# Diagrama_prima_rio_NOVO.net
KiCad netlist of a schematic drawn in EAGLE
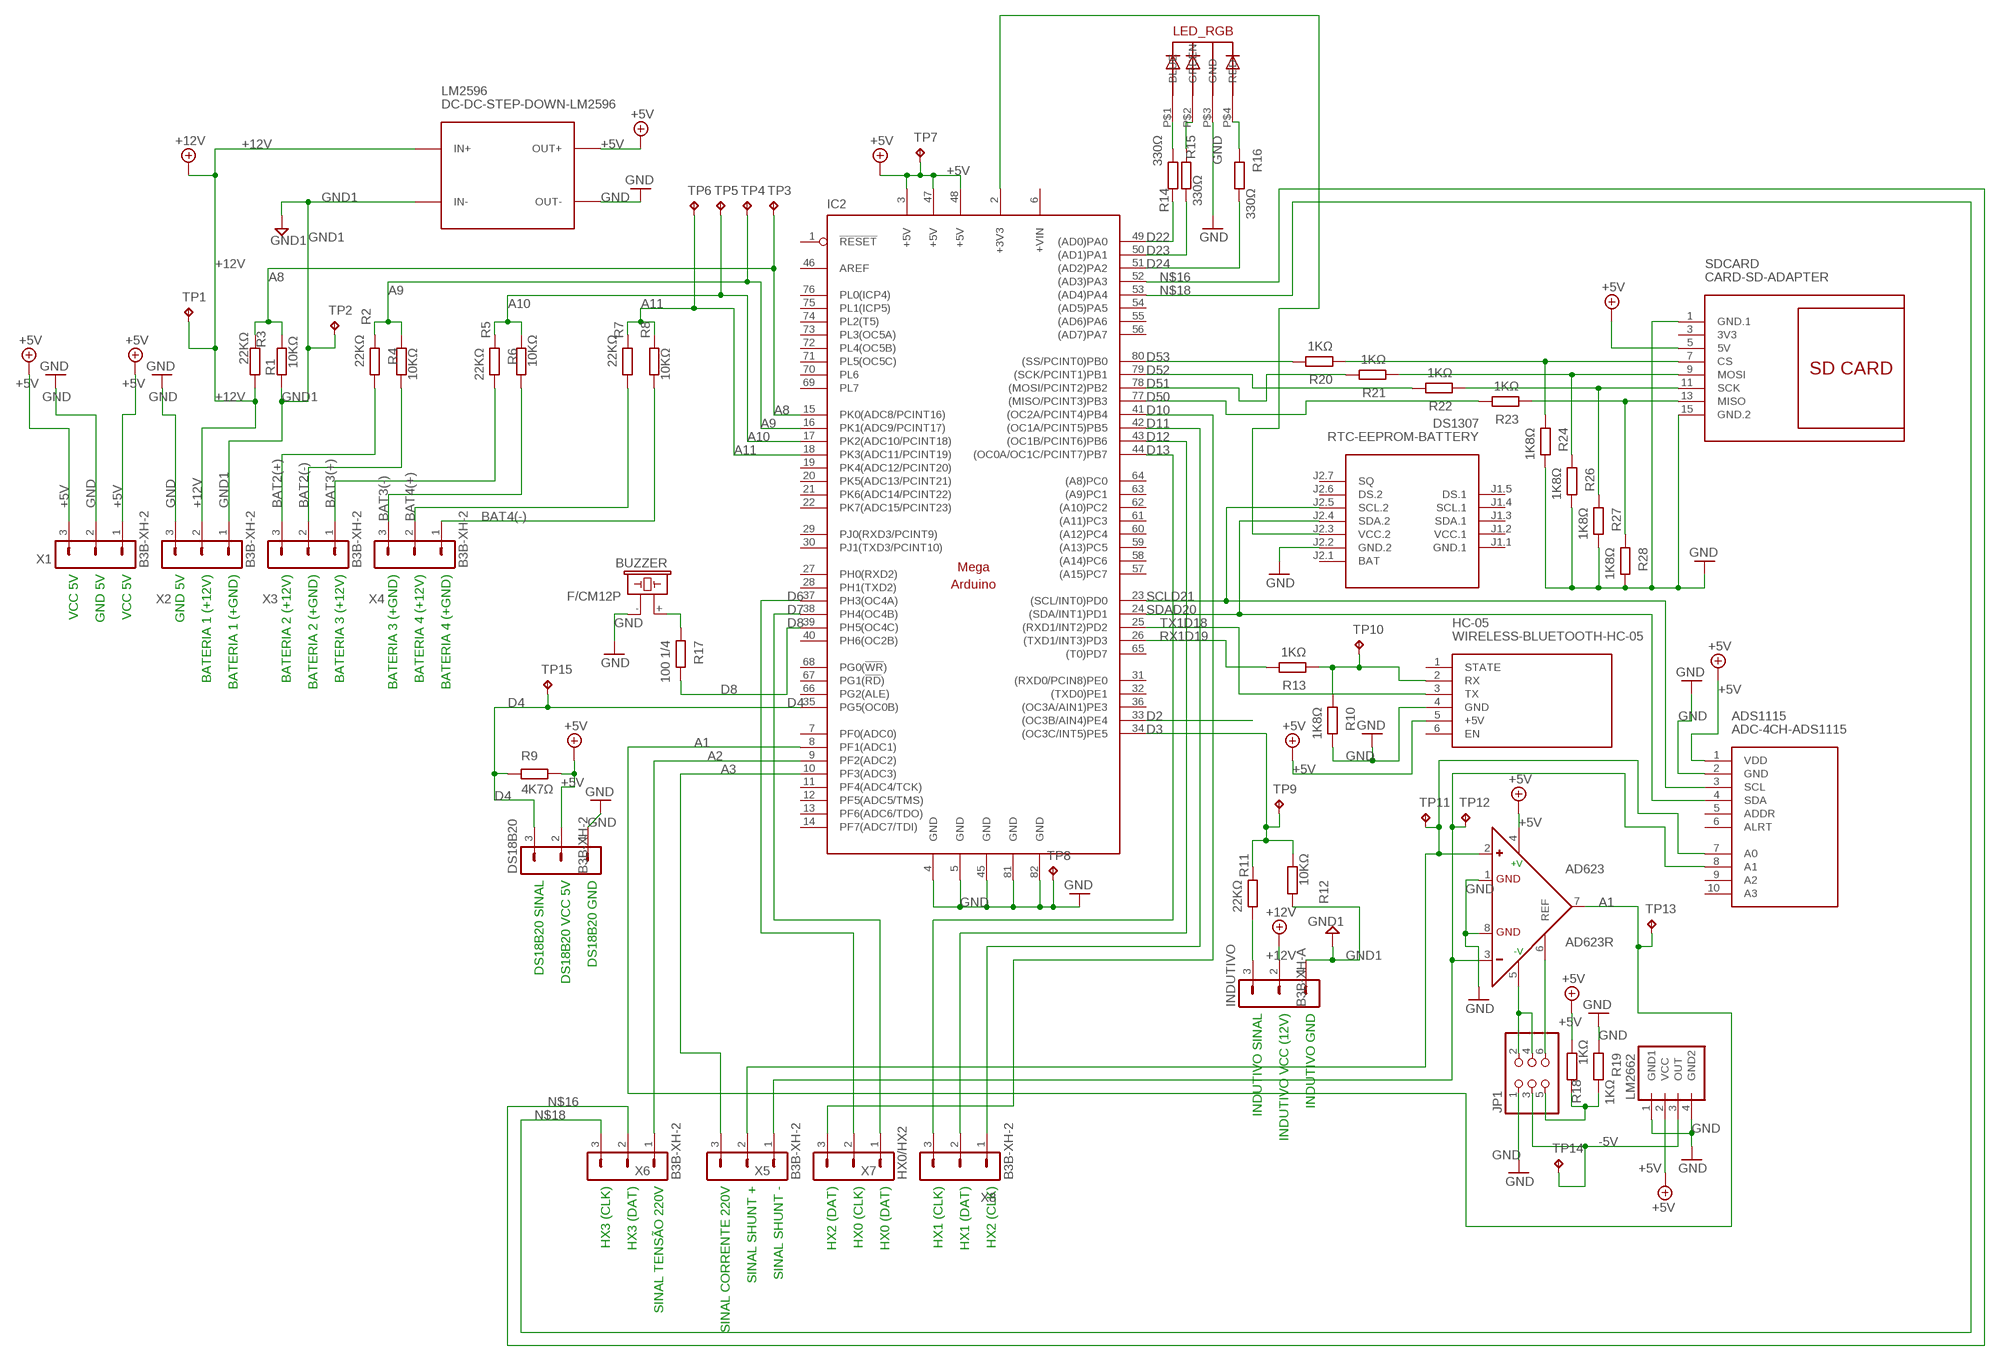
[diagram p0: schematic, sheet 1]

(export (version "E")
  (design (tool "Eeschema 10.0.6"))
  (components
    (comp (ref "AD623")
      (value "AD623R")
      (footprint "eagle-import:SO8")
      (fields (field (name "MPN") "AD623ARZ."))
      (libsource (lib "eagle-import") (part "AD623R"))
    )
    (comp (ref "ADS1115")
      (value "ADC-4CH-ADS1115")
      (footprint "eagle-import:ADC-4CH-ADS1115")
      (libsource (lib "eagle-import") (part "ADC-4CH-ADS1115"))
    )
    (comp (ref "BUZZER")
      (value "F/CM12P")
      (footprint "eagle-import:F_CM12P")
      (libsource (lib "eagle-import") (part "F/CM12P"))
    )
    (comp (ref "DS18B20")
      (value "B3B-XH-2")
      (footprint "eagle-import:B3B-XH-A")
      (libsource (lib "eagle-import") (part "B3B-XH-2"))
    )
    (comp (ref "DS1307")
      (value "RTC-EEPROM-BATTERY")
      (footprint "eagle-import:RTC-EEPROM-BATTERY")
      (libsource (lib "eagle-import") (part "RTC-EEPROM-BATTERY"))
    )
    (comp (ref "HC-05")
      (value "WIRELESS-BLUETOOTH-HC-05")
      (footprint "eagle-import:WIRELESS-BLUETOOTH-HC-05")
      (libsource (lib "eagle-import") (part "WIRELESS-BLUETOOTH-HC-05"))
    )
    (comp (ref "IC2")
      (value "MEGAARDUINO_11")
      (footprint "eagle-import:MEGA_ARDUINO_1")
      (libsource (lib "eagle-import") (part "MEGAARDUINO_11"))
    )
    (comp (ref "INDUTIVO")
      (value "B3B-XH-A")
      (footprint "eagle-import:B3B-XH-A")
      (libsource (lib "eagle-import") (part "con-JST XH_14082343_B3B-XH-A"))
    )
    (comp (ref "JP1")
      (value "PINHD-2X3")
      (footprint "eagle-import:2X03")
      (libsource (lib "eagle-import") (part "PINHD-2X3"))
    )
    (comp (ref "LED_RGB")
      (value "5MMRGBLED")
      (footprint "eagle-import:LED5MMRGB")
      (libsource (lib "eagle-import") (part "5MMRGBLED"))
    )
    (comp (ref "LM2596")
      (value "DC-DC-STEP-DOWN-LM2596")
      (footprint "eagle-import:DC-DC-STEP-DOWN-LM2596")
      (libsource (lib "eagle-import") (part "DC-DC-STEP-DOWN-LM2596"))
    )
    (comp (ref "LM2662")
      (value "LM2662")
      (footprint "eagle-import:LM2662")
      (libsource (lib "eagle-import") (part "LM2662"))
    )
    (comp (ref "R1")
      (value "10KΩ")
      (footprint "eagle-import:1_4W-0.41K")
      (libsource (lib "eagle-import") (part "1K1/4RESISTOR"))
    )
    (comp (ref "R2")
      (value "22KΩ")
      (footprint "eagle-import:1_4W-0.41K")
      (libsource (lib "eagle-import") (part "1K1/4RESISTOR"))
    )
    (comp (ref "R3")
      (value "22KΩ")
      (footprint "eagle-import:1_4W-0.41K")
      (libsource (lib "eagle-import") (part "1K1/4RESISTOR"))
    )
    (comp (ref "R4")
      (value "10KΩ")
      (footprint "eagle-import:1_4W-0.41K")
      (libsource (lib "eagle-import") (part "1K1/4RESISTOR"))
    )
    (comp (ref "R5")
      (value "22KΩ")
      (footprint "eagle-import:1_4W-0.41K")
      (libsource (lib "eagle-import") (part "1K1/4RESISTOR"))
    )
    (comp (ref "R6")
      (value "10KΩ")
      (footprint "eagle-import:1_4W-0.41K")
      (libsource (lib "eagle-import") (part "1K1/4RESISTOR"))
    )
    (comp (ref "R7")
      (value "22KΩ")
      (footprint "eagle-import:1_4W-0.41K")
      (libsource (lib "eagle-import") (part "1K1/4RESISTOR"))
    )
    (comp (ref "R8")
      (value "10KΩ")
      (footprint "eagle-import:1_4W-0.41K")
      (libsource (lib "eagle-import") (part "1K1/4RESISTOR"))
    )
    (comp (ref "R9")
      (value "4K7Ω")
      (footprint "eagle-import:1_4W-0.41K")
      (libsource (lib "eagle-import") (part "1K1/4RESISTOR"))
    )
    (comp (ref "R10")
      (value "1K8Ω")
      (footprint "eagle-import:1_4W-0.41K")
      (libsource (lib "eagle-import") (part "1K1/4RESISTOR"))
    )
    (comp (ref "R11")
      (value "22KΩ")
      (footprint "eagle-import:1_4W-0.41K")
      (libsource (lib "eagle-import") (part "1K1/4RESISTOR"))
    )
    (comp (ref "R12")
      (value "10KΩ")
      (footprint "eagle-import:1_4W-0.41K")
      (libsource (lib "eagle-import") (part "1K1/4RESISTOR"))
    )
    (comp (ref "R13")
      (value "1KΩ")
      (footprint "eagle-import:1_4W-0.41K")
      (libsource (lib "eagle-import") (part "1K1/4RESISTOR"))
    )
    (comp (ref "R14")
      (value "330Ω")
      (footprint "eagle-import:1_4W-0.41K")
      (libsource (lib "eagle-import") (part "1K1/4RESISTOR"))
    )
    (comp (ref "R15")
      (value "330Ω")
      (footprint "eagle-import:1_4W-0.41K")
      (libsource (lib "eagle-import") (part "1K1/4RESISTOR"))
    )
    (comp (ref "R16")
      (value "330Ω")
      (footprint "eagle-import:1_4W-0.41K")
      (libsource (lib "eagle-import") (part "1K1/4RESISTOR"))
    )
    (comp (ref "R17")
      (value "100 1/4")
      (footprint "eagle-import:1_4W-0.41K")
      (libsource (lib "eagle-import") (part "1K1/4RESISTOR"))
    )
    (comp (ref "R18")
      (value "1KΩ")
      (footprint "eagle-import:1_4W-0.41K")
      (libsource (lib "eagle-import") (part "1K1/4RESISTOR"))
    )
    (comp (ref "R19")
      (value "1KΩ")
      (footprint "eagle-import:1_4W-0.41K")
      (libsource (lib "eagle-import") (part "1K1/4RESISTOR"))
    )
    (comp (ref "R20")
      (value "1KΩ")
      (footprint "eagle-import:1_4W-0.41K")
      (libsource (lib "eagle-import") (part "1K1/4RESISTOR"))
    )
    (comp (ref "R21")
      (value "1KΩ")
      (footprint "eagle-import:1_4W-0.41K")
      (libsource (lib "eagle-import") (part "1K1/4RESISTOR"))
    )
    (comp (ref "R22")
      (value "1KΩ")
      (footprint "eagle-import:1_4W-0.41K")
      (libsource (lib "eagle-import") (part "1K1/4RESISTOR"))
    )
    (comp (ref "R23")
      (value "1KΩ")
      (footprint "eagle-import:1_4W-0.41K")
      (libsource (lib "eagle-import") (part "1K1/4RESISTOR"))
    )
    (comp (ref "R24")
      (value "1K8Ω")
      (footprint "eagle-import:1_4W-0.41K")
      (libsource (lib "eagle-import") (part "1K1/4RESISTOR"))
    )
    (comp (ref "R26")
      (value "1K8Ω")
      (footprint "eagle-import:1_4W-0.41K")
      (libsource (lib "eagle-import") (part "1K1/4RESISTOR"))
    )
    (comp (ref "R27")
      (value "1K8Ω")
      (footprint "eagle-import:1_4W-0.41K")
      (libsource (lib "eagle-import") (part "1K1/4RESISTOR"))
    )
    (comp (ref "R28")
      (value "1K8Ω")
      (footprint "eagle-import:1_4W-0.41K")
      (libsource (lib "eagle-import") (part "1K1/4RESISTOR"))
    )
    (comp (ref "SDCARD")
      (value "CARD-SD-ADAPTER")
      (footprint "eagle-import:CARD-SD-ADAPTER")
      (libsource (lib "eagle-import") (part "CARD-SD-ADAPTER"))
    )
    (comp (ref "TP1")
      (value "TPB1,27")
      (footprint "eagle-import:B1,27")
      (libsource (lib "eagle-import") (part "TPB1,27"))
    )
    (comp (ref "TP2")
      (value "TPB1,27")
      (footprint "eagle-import:B1,27")
      (libsource (lib "eagle-import") (part "TPB1,27"))
    )
    (comp (ref "TP3")
      (value "TPB1,27")
      (footprint "eagle-import:B1,27")
      (libsource (lib "eagle-import") (part "TPB1,27"))
    )
    (comp (ref "TP4")
      (value "TPB1,27")
      (footprint "eagle-import:B1,27")
      (libsource (lib "eagle-import") (part "TPB1,27"))
    )
    (comp (ref "TP5")
      (value "TPB1,27")
      (footprint "eagle-import:B1,27")
      (libsource (lib "eagle-import") (part "TPB1,27"))
    )
    (comp (ref "TP6")
      (value "TPB1,27")
      (footprint "eagle-import:B1,27")
      (libsource (lib "eagle-import") (part "TPB1,27"))
    )
    (comp (ref "TP7")
      (value "TPB1,27")
      (footprint "eagle-import:B1,27")
      (libsource (lib "eagle-import") (part "TPB1,27"))
    )
    (comp (ref "TP8")
      (value "TPB1,27")
      (footprint "eagle-import:B1,27")
      (libsource (lib "eagle-import") (part "TPB1,27"))
    )
    (comp (ref "TP9")
      (value "TPB1,27")
      (footprint "eagle-import:B1,27")
      (libsource (lib "eagle-import") (part "TPB1,27"))
    )
    (comp (ref "TP10")
      (value "TPB1,27")
      (footprint "eagle-import:B1,27")
      (libsource (lib "eagle-import") (part "TPB1,27"))
    )
    (comp (ref "TP11")
      (value "TPB1,27")
      (footprint "eagle-import:B1,27")
      (libsource (lib "eagle-import") (part "TPB1,27"))
    )
    (comp (ref "TP12")
      (value "TPB1,27")
      (footprint "eagle-import:B1,27")
      (libsource (lib "eagle-import") (part "TPB1,27"))
    )
    (comp (ref "TP13")
      (value "TPB1,27")
      (footprint "eagle-import:B1,27")
      (libsource (lib "eagle-import") (part "TPB1,27"))
    )
    (comp (ref "TP14")
      (value "TPB1,27")
      (footprint "eagle-import:B1,27")
      (libsource (lib "eagle-import") (part "TPB1,27"))
    )
    (comp (ref "TP15")
      (value "TPB1,27")
      (footprint "eagle-import:B1,27")
      (libsource (lib "eagle-import") (part "TPB1,27"))
    )
    (comp (ref "X1")
      (value "B3B-XH-2")
      (footprint "eagle-import:B3B-XH-A")
      (libsource (lib "eagle-import") (part "con-JST XH_14082343_B3B-XH-2"))
    )
    (comp (ref "X2")
      (value "B3B-XH-2")
      (footprint "eagle-import:B3B-XH-A")
      (libsource (lib "eagle-import") (part "con-JST XH_14082343_B3B-XH-2"))
    )
    (comp (ref "X3")
      (value "B3B-XH-2")
      (footprint "eagle-import:B3B-XH-A")
      (libsource (lib "eagle-import") (part "con-JST XH_14082343_B3B-XH-2"))
    )
    (comp (ref "X4")
      (value "B3B-XH-2")
      (footprint "eagle-import:B3B-XH-A")
      (libsource (lib "eagle-import") (part "con-JST XH_14082343_B3B-XH-2"))
    )
    (comp (ref "X5")
      (value "B3B-XH-2")
      (footprint "eagle-import:B3B-XH-A")
      (libsource (lib "eagle-import") (part "con-JST XH_14082343_B3B-XH-2"))
    )
    (comp (ref "X6")
      (value "B3B-XH-2")
      (footprint "eagle-import:B3B-XH-A")
      (libsource (lib "eagle-import") (part "con-JST XH_14082343_B3B-XH-2"))
    )
    (comp (ref "X7")
      (value "HX0/HX2")
      (footprint "eagle-import:B3B-XH-A")
      (libsource (lib "eagle-import") (part "con-JST XH_14082343_B3B-XH-2"))
    )
    (comp (ref "X8")
      (value "B3B-XH-2")
      (footprint "eagle-import:B3B-XH-A")
      (libsource (lib "eagle-import") (part "con-JST XH_14082343_B3B-XH-2"))
    )
  )
  (nets
    (net (code "1") (name "+5V") (class "Default")
      (node (ref "AD623") (pin "4") (pinfunction "+V_4") (pintype "power_in"))
      (node (ref "ADS1115") (pin "1") (pinfunction "VDD_1") (pintype "power_in"))
      (node (ref "DS18B20") (pin "2") (pinfunction "2_2") (pintype "passive"))
      (node (ref "HC-05") (pin "5") (pinfunction "+5V_5") (pintype "power_in"))
      (node (ref "IC2") (pin "3") (pinfunction "+5V_3") (pintype "power_in"))
      (node (ref "IC2") (pin "47") (pinfunction "+5V_47") (pintype "power_in"))
      (node (ref "IC2") (pin "48") (pinfunction "+5V_48") (pintype "power_in"))
      (node (ref "LM2596") (pin "OUT+") (pinfunction "OUT+_OUT+") (pintype "bidirectional"))
      (node (ref "LM2662") (pin "2") (pinfunction "VCC_2") (pintype "bidirectional"))
      (node (ref "R18") (pin "1") (pinfunction "1_1") (pintype "passive"))
      (node (ref "R9") (pin "2") (pinfunction "2_2") (pintype "passive"))
      (node (ref "SDCARD") (pin "5") (pinfunction "5V_5") (pintype "power_in"))
      (node (ref "TP7") (pin "TP") (pinfunction "TP_TP") (pintype "input"))
      (node (ref "X1") (pin "1") (pinfunction "1_1") (pintype "passive"))
      (node (ref "X1") (pin "3") (pinfunction "3_3") (pintype "passive"))
    )
    (net (code "2") (name "+12V") (class "Default")
      (node (ref "INDUTIVO") (pin "2") (pinfunction "2_2") (pintype "passive"))
      (node (ref "LM2596") (pin "IN+") (pinfunction "IN+_IN+") (pintype "bidirectional"))
      (node (ref "R3") (pin "2") (pinfunction "2_2") (pintype "passive"))
      (node (ref "TP1") (pin "TP") (pinfunction "TP_TP") (pintype "input"))
      (node (ref "X2") (pin "2") (pinfunction "2_2") (pintype "passive"))
    )
    (net (code "3") (name "/+VIN") (class "Default")
      (node (ref "IC2") (pin "6") (pinfunction "+VIN_6") (pintype "power_in"))
    )
    (net (code "4") (name "/-5V") (class "Default")
      (node (ref "JP1") (pin "3") (pinfunction "3_3") (pintype "passive"))
      (node (ref "LM2662") (pin "3") (pinfunction "OUT_3") (pintype "bidirectional"))
      (node (ref "TP14") (pin "TP") (pinfunction "TP_TP") (pintype "input"))
    )
    (net (code "5") (name "/3V3") (class "Default")
      (node (ref "SDCARD") (pin "3") (pinfunction "3V3_3") (pintype "power_in"))
    )
    (net (code "6") (name "/A1") (class "Default")
      (node (ref "AD623") (pin "7") (pinfunction "OUT_7") (pintype "output"))
      (node (ref "IC2") (pin "8") (pinfunction "PF1(ADC1)_8") (pintype "bidirectional"))
      (node (ref "TP13") (pin "TP") (pinfunction "TP_TP") (pintype "input"))
    )
    (net (code "7") (name "/A2") (class "Default")
      (node (ref "IC2") (pin "9") (pinfunction "PF2(ADC2)_9") (pintype "bidirectional"))
      (node (ref "X6") (pin "1") (pinfunction "1_1") (pintype "passive"))
    )
    (net (code "8") (name "/A3") (class "Default")
      (node (ref "IC2") (pin "10") (pinfunction "PF3(ADC3)_10") (pintype "bidirectional"))
      (node (ref "X5") (pin "3") (pinfunction "3_3") (pintype "passive"))
    )
    (net (code "9") (name "/A8") (class "Default")
      (node (ref "IC2") (pin "15") (pinfunction "PK0(ADC8/PCINT16)_15") (pintype "bidirectional"))
      (node (ref "R1") (pin "1") (pinfunction "1_1") (pintype "passive"))
      (node (ref "R3") (pin "1") (pinfunction "1_1") (pintype "passive"))
      (node (ref "TP3") (pin "TP") (pinfunction "TP_TP") (pintype "input"))
    )
    (net (code "10") (name "/A9") (class "Default")
      (node (ref "IC2") (pin "16") (pinfunction "PK1(ADC9/PCINT17)_16") (pintype "bidirectional"))
      (node (ref "R2") (pin "1") (pinfunction "1_1") (pintype "passive"))
      (node (ref "R4") (pin "1") (pinfunction "1_1") (pintype "passive"))
      (node (ref "TP4") (pin "TP") (pinfunction "TP_TP") (pintype "input"))
    )
    (net (code "11") (name "/A10") (class "Default")
      (node (ref "IC2") (pin "17") (pinfunction "PK2(ADC10/PCINT18)_17") (pintype "bidirectional"))
      (node (ref "R5") (pin "1") (pinfunction "1_1") (pintype "passive"))
      (node (ref "R6") (pin "1") (pinfunction "1_1") (pintype "passive"))
      (node (ref "TP5") (pin "TP") (pinfunction "TP_TP") (pintype "input"))
    )
    (net (code "12") (name "/A11") (class "Default")
      (node (ref "IC2") (pin "18") (pinfunction "PK3(ADC11/PCINT19)_18") (pintype "bidirectional"))
      (node (ref "R7") (pin "1") (pinfunction "1_1") (pintype "passive"))
      (node (ref "R8") (pin "1") (pinfunction "1_1") (pintype "passive"))
      (node (ref "TP6") (pin "TP") (pinfunction "TP_TP") (pintype "input"))
    )
    (net (code "13") (name "/BAT2(+)") (class "Default")
      (node (ref "R2") (pin "2") (pinfunction "2_2") (pintype "passive"))
      (node (ref "X3") (pin "3") (pinfunction "3_3") (pintype "passive"))
    )
    (net (code "14") (name "/BAT2(-)") (class "Default")
      (node (ref "R4") (pin "2") (pinfunction "2_2") (pintype "passive"))
      (node (ref "X3") (pin "2") (pinfunction "2_2") (pintype "passive"))
    )
    (net (code "15") (name "/BAT3(+)") (class "Default")
      (node (ref "R5") (pin "2") (pinfunction "2_2") (pintype "passive"))
      (node (ref "X3") (pin "1") (pinfunction "1_1") (pintype "passive"))
    )
    (net (code "16") (name "/BAT3(-)") (class "Default")
      (node (ref "R6") (pin "2") (pinfunction "2_2") (pintype "passive"))
      (node (ref "X4") (pin "3") (pinfunction "3_3") (pintype "passive"))
    )
    (net (code "17") (name "/BAT4(+)") (class "Default")
      (node (ref "R7") (pin "2") (pinfunction "2_2") (pintype "passive"))
      (node (ref "X4") (pin "2") (pinfunction "2_2") (pintype "passive"))
    )
    (net (code "18") (name "/BAT4(-)") (class "Default")
      (node (ref "R8") (pin "2") (pinfunction "2_2") (pintype "passive"))
      (node (ref "X4") (pin "1") (pinfunction "1_1") (pintype "passive"))
    )
    (net (code "19") (name "/D2") (class "Default")
      (node (ref "IC2") (pin "33") (pinfunction "(OC3B/AIN4)PE4_33") (pintype "bidirectional"))
    )
    (net (code "20") (name "/D3") (class "Default")
      (node (ref "IC2") (pin "34") (pinfunction "(OC3C/INT5)PE5_34") (pintype "bidirectional"))
      (node (ref "R11") (pin "1") (pinfunction "1_1") (pintype "passive"))
      (node (ref "R12") (pin "1") (pinfunction "1_1") (pintype "passive"))
      (node (ref "TP9") (pin "TP") (pinfunction "TP_TP") (pintype "input"))
    )
    (net (code "21") (name "/D4") (class "Default")
      (node (ref "DS18B20") (pin "3") (pinfunction "3_3") (pintype "passive"))
      (node (ref "IC2") (pin "35") (pinfunction "PG5(OC0B)_35") (pintype "bidirectional"))
      (node (ref "R9") (pin "1") (pinfunction "1_1") (pintype "passive"))
      (node (ref "TP15") (pin "TP") (pinfunction "TP_TP") (pintype "input"))
    )
    (net (code "22") (name "/D6") (class "Default")
      (node (ref "IC2") (pin "37") (pinfunction "PH3(OC4A)_37") (pintype "bidirectional"))
      (node (ref "X7") (pin "2") (pinfunction "2_2") (pintype "passive"))
    )
    (net (code "23") (name "/D7") (class "Default")
      (node (ref "IC2") (pin "38") (pinfunction "PH4(OC4B)_38") (pintype "bidirectional"))
      (node (ref "X7") (pin "1") (pinfunction "1_1") (pintype "passive"))
    )
    (net (code "24") (name "/D8") (class "Default")
      (node (ref "IC2") (pin "39") (pinfunction "PH5(OC4C)_39") (pintype "bidirectional"))
      (node (ref "R17") (pin "2") (pinfunction "2_2") (pintype "passive"))
    )
    (net (code "25") (name "/D10") (class "Default")
      (node (ref "IC2") (pin "41") (pinfunction "(OC2A/PCINT4)PB4_41") (pintype "bidirectional"))
      (node (ref "X7") (pin "3") (pinfunction "3_3") (pintype "passive"))
    )
    (net (code "26") (name "/D11") (class "Default")
      (node (ref "IC2") (pin "42") (pinfunction "(OC1A/PCINT5)PB5_42") (pintype "bidirectional"))
      (node (ref "X8") (pin "1") (pinfunction "1_1") (pintype "passive"))
    )
    (net (code "27") (name "/D12") (class "Default")
      (node (ref "IC2") (pin "43") (pinfunction "(OC1B/PCINT6)PB6_43") (pintype "bidirectional"))
      (node (ref "X8") (pin "2") (pinfunction "2_2") (pintype "passive"))
    )
    (net (code "28") (name "/D13") (class "Default")
      (node (ref "IC2") (pin "44") (pinfunction "(OC0A/OC1C/PCINT7)PB7_44") (pintype "bidirectional"))
      (node (ref "X8") (pin "3") (pinfunction "3_3") (pintype "passive"))
    )
    (net (code "29") (name "/D22") (class "Default")
      (node (ref "IC2") (pin "49") (pinfunction "(AD0)PA0_49") (pintype "bidirectional"))
      (node (ref "R14") (pin "2") (pinfunction "2_2") (pintype "passive"))
    )
    (net (code "30") (name "/D23") (class "Default")
      (node (ref "IC2") (pin "50") (pinfunction "(AD1)PA1_50") (pintype "bidirectional"))
      (node (ref "R15") (pin "2") (pinfunction "2_2") (pintype "passive"))
    )
    (net (code "31") (name "/D24") (class "Default")
      (node (ref "IC2") (pin "51") (pinfunction "(AD2)PA2_51") (pintype "bidirectional"))
      (node (ref "R16") (pin "2") (pinfunction "2_2") (pintype "passive"))
    )
    (net (code "32") (name "/D50") (class "Default")
      (node (ref "IC2") (pin "77") (pinfunction "(MISO/PCINT3)PB3_77") (pintype "bidirectional"))
      (node (ref "R23") (pin "2") (pinfunction "2_2") (pintype "passive"))
    )
    (net (code "33") (name "/D51") (class "Default")
      (node (ref "IC2") (pin "78") (pinfunction "(MOSI/PCINT2)PB2_78") (pintype "bidirectional"))
      (node (ref "R21") (pin "1") (pinfunction "1_1") (pintype "passive"))
      (node (ref "R21") (pin "2") (pinfunction "2_2") (pintype "passive"))
      (node (ref "R26") (pin "1") (pinfunction "1_1") (pintype "passive"))
      (node (ref "SDCARD") (pin "9") (pinfunction "MOSI_9") (pintype "bidirectional"))
    )
    (net (code "34") (name "/D52") (class "Default")
      (node (ref "IC2") (pin "79") (pinfunction "(SCK/PCINT1)PB1_79") (pintype "bidirectional"))
      (node (ref "R22") (pin "2") (pinfunction "2_2") (pintype "passive"))
    )
    (net (code "35") (name "/D53") (class "Default")
      (node (ref "IC2") (pin "80") (pinfunction "(SS/PCINT0)PB0_80") (pintype "bidirectional"))
      (node (ref "R20") (pin "1") (pinfunction "1_1") (pintype "passive"))
      (node (ref "R20") (pin "2") (pinfunction "2_2") (pintype "passive"))
      (node (ref "R24") (pin "1") (pinfunction "1_1") (pintype "passive"))
      (node (ref "SDCARD") (pin "7") (pinfunction "CS_7") (pintype "bidirectional"))
    )
    (net (code "36") (name "/GND.1") (class "Default")
      (node (ref "DS1307") (pin "J1.1") (pinfunction "GND.1_J1.1") (pintype "power_in"))
    )
    (net (code "37") (name "/N$16") (class "Default")
      (node (ref "IC2") (pin "52") (pinfunction "(AD3)PA3_52") (pintype "bidirectional"))
      (node (ref "X6") (pin "2") (pinfunction "2_2") (pintype "passive"))
    )
    (net (code "38") (name "/N$18") (class "Default")
      (node (ref "IC2") (pin "53") (pinfunction "(AD4)PA4_53") (pintype "bidirectional"))
      (node (ref "X6") (pin "3") (pinfunction "3_3") (pintype "passive"))
    )
    (net (code "39") (name "/RX1D19") (class "Default")
      (node (ref "IC2") (pin "26") (pinfunction "(TXD1/INT3)PD3_26") (pintype "bidirectional"))
      (node (ref "R13") (pin "2") (pinfunction "2_2") (pintype "passive"))
    )
    (net (code "40") (name "/SCLD21") (class "Default")
      (node (ref "ADS1115") (pin "3") (pinfunction "SCL_3") (pintype "bidirectional"))
      (node (ref "DS1307") (pin "J2.5") (pinfunction "SCL.2_J2.5") (pintype "bidirectional"))
      (node (ref "IC2") (pin "23") (pinfunction "(SCL/INT0)PD0_23") (pintype "bidirectional"))
    )
    (net (code "41") (name "/SDAD20") (class "Default")
      (node (ref "ADS1115") (pin "4") (pinfunction "SDA_4") (pintype "bidirectional"))
      (node (ref "DS1307") (pin "J2.4") (pinfunction "SDA.2_J2.4") (pintype "bidirectional"))
      (node (ref "IC2") (pin "24") (pinfunction "(SDA/INT1)PD1_24") (pintype "bidirectional"))
    )
    (net (code "42") (name "/TX1D18") (class "Default")
      (node (ref "HC-05") (pin "3") (pinfunction "TX_3") (pintype "bidirectional"))
      (node (ref "IC2") (pin "25") (pinfunction "(RXD1/INT2)PD2_25") (pintype "bidirectional"))
    )
    (net (code "43") (name "/VCC.1") (class "Default")
      (node (ref "DS1307") (pin "J1.2") (pinfunction "VCC.1_J1.2") (pintype "power_in"))
    )
    (net (code "44") (name "GND") (class "Default")
      (node (ref "AD623") (pin "1") (pinfunction "RG_1") (pintype "passive"))
      (node (ref "AD623") (pin "8") (pinfunction "RG_8") (pintype "passive"))
      (node (ref "ADS1115") (pin "2") (pinfunction "GND_2") (pintype "power_in"))
      (node (ref "BUZZER") (pin "-") (pinfunction "2_-") (pintype "passive"))
      (node (ref "DS1307") (pin "J2.2") (pinfunction "GND.2_J2.2") (pintype "power_in"))
      (node (ref "DS18B20") (pin "1") (pinfunction "1_1") (pintype "passive"))
      (node (ref "HC-05") (pin "4") (pinfunction "GND_4") (pintype "power_in"))
      (node (ref "IC2") (pin "4") (pinfunction "GND_4") (pintype "power_in"))
      (node (ref "IC2") (pin "45") (pinfunction "GND_45") (pintype "power_in"))
      (node (ref "IC2") (pin "5") (pinfunction "GND_5") (pintype "power_in"))
      (node (ref "IC2") (pin "81") (pinfunction "GND_81") (pintype "power_in"))
      (node (ref "IC2") (pin "82") (pinfunction "GND_82") (pintype "power_in"))
      (node (ref "JP1") (pin "1") (pinfunction "1_1") (pintype "passive"))
      (node (ref "LED_RGB") (pin "P$3") (pinfunction "GND_P$3") (pintype "bidirectional"))
      (node (ref "LM2596") (pin "OUT-") (pinfunction "OUT-_OUT-") (pintype "bidirectional"))
      (node (ref "LM2662") (pin "1") (pinfunction "GND1_1") (pintype "bidirectional"))
      (node (ref "LM2662") (pin "4") (pinfunction "GND2_4") (pintype "bidirectional"))
      (node (ref "R10") (pin "2") (pinfunction "2_2") (pintype "passive"))
      (node (ref "R19") (pin "1") (pinfunction "1_1") (pintype "passive"))
      (node (ref "R24") (pin "2") (pinfunction "2_2") (pintype "passive"))
      (node (ref "R26") (pin "2") (pinfunction "2_2") (pintype "passive"))
      (node (ref "R27") (pin "2") (pinfunction "2_2") (pintype "passive"))
      (node (ref "R28") (pin "2") (pinfunction "2_2") (pintype "passive"))
      (node (ref "SDCARD") (pin "1") (pinfunction "GND.1_1") (pintype "power_in"))
      (node (ref "SDCARD") (pin "15") (pinfunction "GND.2_15") (pintype "power_in"))
      (node (ref "TP8") (pin "TP") (pinfunction "TP_TP") (pintype "input"))
      (node (ref "X1") (pin "2") (pinfunction "2_2") (pintype "passive"))
      (node (ref "X2") (pin "3") (pinfunction "3_3") (pintype "passive"))
    )
    (net (code "45") (name "GND1") (class "Default")
      (node (ref "INDUTIVO") (pin "1") (pinfunction "1_1") (pintype "passive"))
      (node (ref "LM2596") (pin "IN-") (pinfunction "IN-_IN-") (pintype "bidirectional"))
      (node (ref "R1") (pin "2") (pinfunction "2_2") (pintype "passive"))
      (node (ref "R12") (pin "2") (pinfunction "2_2") (pintype "passive"))
      (node (ref "TP2") (pin "TP") (pinfunction "TP_TP") (pintype "input"))
      (node (ref "X2") (pin "1") (pinfunction "1_1") (pintype "passive"))
    )
    (net (code "46") (name "Net-(AD623-+)") (class "Default")
      (node (ref "AD623") (pin "2") (pinfunction "+_2") (pintype "input"))
      (node (ref "ADS1115") (pin "7") (pinfunction "A0_7") (pintype "input"))
      (node (ref "TP11") (pin "TP") (pinfunction "TP_TP") (pintype "input"))
      (node (ref "X5") (pin "2") (pinfunction "2_2") (pintype "passive"))
    )
    (net (code "47") (name "Net-(AD623--)") (class "Default")
      (node (ref "AD623") (pin "3") (pinfunction "-_3") (pintype "input"))
      (node (ref "ADS1115") (pin "8") (pinfunction "A1_8") (pintype "input"))
      (node (ref "TP12") (pin "TP") (pinfunction "TP_TP") (pintype "input"))
      (node (ref "X5") (pin "1") (pinfunction "1_1") (pintype "passive"))
    )
    (net (code "48") (name "Net-(AD623--V)") (class "Default")
      (node (ref "AD623") (pin "5") (pinfunction "-V_5") (pintype "power_in"))
      (node (ref "JP1") (pin "2") (pinfunction "2_2") (pintype "passive"))
      (node (ref "JP1") (pin "4") (pinfunction "4_4") (pintype "passive"))
    )
    (net (code "49") (name "Net-(AD623-REF)") (class "Default")
      (node (ref "AD623") (pin "6") (pinfunction "REF_6") (pintype "passive"))
      (node (ref "JP1") (pin "6") (pinfunction "6_6") (pintype "passive"))
    )
    (net (code "50") (name "Net-(BUZZER-1)") (class "Default")
      (node (ref "BUZZER") (pin "+") (pinfunction "1_+") (pintype "passive"))
      (node (ref "R17") (pin "1") (pinfunction "1_1") (pintype "passive"))
    )
    (net (code "51") (name "Net-(DS1307-VCC.2)") (class "Default")
      (node (ref "DS1307") (pin "J2.3") (pinfunction "VCC.2_J2.3") (pintype "power_in"))
      (node (ref "IC2") (pin "2") (pinfunction "+3V3_2") (pintype "power_in"))
    )
    (net (code "52") (name "Net-(HC-05-RX)") (class "Default")
      (node (ref "HC-05") (pin "2") (pinfunction "RX_2") (pintype "bidirectional"))
      (node (ref "R10") (pin "1") (pinfunction "1_1") (pintype "passive"))
      (node (ref "R13") (pin "1") (pinfunction "1_1") (pintype "passive"))
      (node (ref "TP10") (pin "TP") (pinfunction "TP_TP") (pintype "input"))
    )
    (net (code "53") (name "Net-(INDUTIVO-Pad3)") (class "Default")
      (node (ref "INDUTIVO") (pin "3") (pinfunction "3_3") (pintype "passive"))
      (node (ref "R11") (pin "2") (pinfunction "2_2") (pintype "passive"))
    )
    (net (code "54") (name "Net-(JP1-Pad5)") (class "Default")
      (node (ref "JP1") (pin "5") (pinfunction "5_5") (pintype "passive"))
      (node (ref "R18") (pin "2") (pinfunction "2_2") (pintype "passive"))
      (node (ref "R19") (pin "2") (pinfunction "2_2") (pintype "passive"))
    )
    (net (code "55") (name "Net-(LED_RGB-BLUE)") (class "Default")
      (node (ref "LED_RGB") (pin "P$1") (pinfunction "BLUE_P$1") (pintype "bidirectional"))
      (node (ref "R14") (pin "1") (pinfunction "1_1") (pintype "passive"))
    )
    (net (code "56") (name "Net-(LED_RGB-GREEN)") (class "Default")
      (node (ref "LED_RGB") (pin "P$2") (pinfunction "GREEN_P$2") (pintype "bidirectional"))
      (node (ref "R15") (pin "1") (pinfunction "1_1") (pintype "passive"))
    )
    (net (code "57") (name "Net-(LED_RGB-RED)") (class "Default")
      (node (ref "LED_RGB") (pin "P$4") (pinfunction "RED_P$4") (pintype "bidirectional"))
      (node (ref "R16") (pin "1") (pinfunction "1_1") (pintype "passive"))
    )
    (net (code "58") (name "Net-(SDCARD-MISO)") (class "Default")
      (node (ref "R23") (pin "1") (pinfunction "1_1") (pintype "passive"))
      (node (ref "R28") (pin "1") (pinfunction "1_1") (pintype "passive"))
      (node (ref "SDCARD") (pin "13") (pinfunction "MISO_13") (pintype "bidirectional"))
    )
    (net (code "59") (name "Net-(SDCARD-SCK)") (class "Default")
      (node (ref "R22") (pin "1") (pinfunction "1_1") (pintype "passive"))
      (node (ref "R27") (pin "1") (pinfunction "1_1") (pintype "passive"))
      (node (ref "SDCARD") (pin "11") (pinfunction "SCK_11") (pintype "bidirectional"))
    )
    (net (code "60") (name "unconnected-(ADS1115-A2-Pad9)") (class "Default")
      (node (ref "ADS1115") (pin "9") (pinfunction "A2_9") (pintype "input"))
    )
    (net (code "61") (name "unconnected-(ADS1115-A3-Pad10)") (class "Default")
      (node (ref "ADS1115") (pin "10") (pinfunction "A3_10") (pintype "input"))
    )
    (net (code "62") (name "unconnected-(ADS1115-ADDR-Pad5)") (class "Default")
      (node (ref "ADS1115") (pin "5") (pinfunction "ADDR_5") (pintype "bidirectional"))
    )
    (net (code "63") (name "unconnected-(ADS1115-ALRT-Pad6)") (class "Default")
      (node (ref "ADS1115") (pin "6") (pinfunction "ALRT_6") (pintype "bidirectional"))
    )
    (net (code "64") (name "unconnected-(DS1307-BAT-PadJ2.1)") (class "Default")
      (node (ref "DS1307") (pin "J2.1") (pinfunction "BAT_J2.1") (pintype "bidirectional"))
    )
    (net (code "65") (name "unconnected-(DS1307-DS.1-PadJ1.5)") (class "Default")
      (node (ref "DS1307") (pin "J1.5") (pinfunction "DS.1_J1.5") (pintype "bidirectional"))
    )
    (net (code "66") (name "unconnected-(DS1307-DS.2-PadJ2.6)") (class "Default")
      (node (ref "DS1307") (pin "J2.6") (pinfunction "DS.2_J2.6") (pintype "bidirectional"))
    )
    (net (code "67") (name "unconnected-(DS1307-SCL.1-PadJ1.4)") (class "Default")
      (node (ref "DS1307") (pin "J1.4") (pinfunction "SCL.1_J1.4") (pintype "bidirectional"))
    )
    (net (code "68") (name "unconnected-(DS1307-SDA.1-PadJ1.3)") (class "Default")
      (node (ref "DS1307") (pin "J1.3") (pinfunction "SDA.1_J1.3") (pintype "bidirectional"))
    )
    (net (code "69") (name "unconnected-(DS1307-SQ-PadJ2.7)") (class "Default")
      (node (ref "DS1307") (pin "J2.7") (pinfunction "SQ_J2.7") (pintype "bidirectional"))
    )
    (net (code "70") (name "unconnected-(HC-05-EN-Pad6)") (class "Default")
      (node (ref "HC-05") (pin "6") (pinfunction "EN_6") (pintype "bidirectional"))
    )
    (net (code "71") (name "unconnected-(HC-05-STATE-Pad1)") (class "Default")
      (node (ref "HC-05") (pin "1") (pinfunction "STATE_1") (pintype "bidirectional"))
    )
    (net (code "72") (name "unconnected-(IC2-(A8)PC0-Pad64)") (class "Default")
      (node (ref "IC2") (pin "64") (pinfunction "(A8)PC0_64") (pintype "bidirectional"))
    )
    (net (code "73") (name "unconnected-(IC2-(A9)PC1-Pad63)") (class "Default")
      (node (ref "IC2") (pin "63") (pinfunction "(A9)PC1_63") (pintype "bidirectional"))
    )
    (net (code "74") (name "unconnected-(IC2-(A10)PC2-Pad62)") (class "Default")
      (node (ref "IC2") (pin "62") (pinfunction "(A10)PC2_62") (pintype "bidirectional"))
    )
    (net (code "75") (name "unconnected-(IC2-(A11)PC3-Pad61)") (class "Default")
      (node (ref "IC2") (pin "61") (pinfunction "(A11)PC3_61") (pintype "bidirectional"))
    )
    (net (code "76") (name "unconnected-(IC2-(A12)PC4-Pad60)") (class "Default")
      (node (ref "IC2") (pin "60") (pinfunction "(A12)PC4_60") (pintype "bidirectional"))
    )
    (net (code "77") (name "unconnected-(IC2-(A13)PC5-Pad59)") (class "Default")
      (node (ref "IC2") (pin "59") (pinfunction "(A13)PC5_59") (pintype "bidirectional"))
    )
    (net (code "78") (name "unconnected-(IC2-(A14)PC6-Pad58)") (class "Default")
      (node (ref "IC2") (pin "58") (pinfunction "(A14)PC6_58") (pintype "bidirectional"))
    )
    (net (code "79") (name "unconnected-(IC2-(A15)PC7-Pad57)") (class "Default")
      (node (ref "IC2") (pin "57") (pinfunction "(A15)PC7_57") (pintype "bidirectional"))
    )
    (net (code "80") (name "unconnected-(IC2-(AD5)PA5-Pad54)") (class "Default")
      (node (ref "IC2") (pin "54") (pinfunction "(AD5)PA5_54") (pintype "bidirectional"))
    )
    (net (code "81") (name "unconnected-(IC2-(AD6)PA6-Pad55)") (class "Default")
      (node (ref "IC2") (pin "55") (pinfunction "(AD6)PA6_55") (pintype "bidirectional"))
    )
    (net (code "82") (name "unconnected-(IC2-(AD7)PA7-Pad56)") (class "Default")
      (node (ref "IC2") (pin "56") (pinfunction "(AD7)PA7_56") (pintype "bidirectional"))
    )
    (net (code "83") (name "unconnected-(IC2-(OC3A{slash}AIN1)PE3-Pad36)") (class "Default")
      (node (ref "IC2") (pin "36") (pinfunction "(OC3A/AIN1)PE3_36") (pintype "bidirectional"))
    )
    (net (code "84") (name "unconnected-(IC2-(RXD0{slash}PCIN8)PE0-Pad31)") (class "Default")
      (node (ref "IC2") (pin "31") (pinfunction "(RXD0/PCIN8)PE0_31") (pintype "bidirectional"))
    )
    (net (code "85") (name "unconnected-(IC2-(T0)PD7-Pad65)") (class "Default")
      (node (ref "IC2") (pin "65") (pinfunction "(T0)PD7_65") (pintype "bidirectional"))
    )
    (net (code "86") (name "unconnected-(IC2-(TXD0)PE1-Pad32)") (class "Default")
      (node (ref "IC2") (pin "32") (pinfunction "(TXD0)PE1_32") (pintype "bidirectional"))
    )
    (net (code "87") (name "unconnected-(IC2-AREF-Pad46)") (class "Default")
      (node (ref "IC2") (pin "46") (pinfunction "AREF_46") (pintype "bidirectional"))
    )
    (net (code "88") (name "unconnected-(IC2-PF0(ADC0)-Pad7)") (class "Default")
      (node (ref "IC2") (pin "7") (pinfunction "PF0(ADC0)_7") (pintype "bidirectional"))
    )
    (net (code "89") (name "unconnected-(IC2-PF4(ADC4{slash}TCK)-Pad11)") (class "Default")
      (node (ref "IC2") (pin "11") (pinfunction "PF4(ADC4/TCK)_11") (pintype "bidirectional"))
    )
    (net (code "90") (name "unconnected-(IC2-PF5(ADC5{slash}TMS)-Pad12)") (class "Default")
      (node (ref "IC2") (pin "12") (pinfunction "PF5(ADC5/TMS)_12") (pintype "bidirectional"))
    )
    (net (code "91") (name "unconnected-(IC2-PF6(ADC6{slash}TDO)-Pad13)") (class "Default")
      (node (ref "IC2") (pin "13") (pinfunction "PF6(ADC6/TDO)_13") (pintype "bidirectional"))
    )
    (net (code "92") (name "unconnected-(IC2-PF7(ADC7{slash}TDI)-Pad14)") (class "Default")
      (node (ref "IC2") (pin "14") (pinfunction "PF7(ADC7/TDI)_14") (pintype "bidirectional"))
    )
    (net (code "93") (name "unconnected-(IC2-PG0(~{WR})-Pad68)") (class "Default")
      (node (ref "IC2") (pin "68") (pinfunction "PG0(~{WR})_68") (pintype "bidirectional"))
    )
    (net (code "94") (name "unconnected-(IC2-PG1(~{RD})-Pad67)") (class "Default")
      (node (ref "IC2") (pin "67") (pinfunction "PG1(~{RD})_67") (pintype "bidirectional"))
    )
    (net (code "95") (name "unconnected-(IC2-PG2(ALE)-Pad66)") (class "Default")
      (node (ref "IC2") (pin "66") (pinfunction "PG2(ALE)_66") (pintype "bidirectional"))
    )
    (net (code "96") (name "unconnected-(IC2-PH0(RXD2)-Pad27)") (class "Default")
      (node (ref "IC2") (pin "27") (pinfunction "PH0(RXD2)_27") (pintype "bidirectional"))
    )
    (net (code "97") (name "unconnected-(IC2-PH1(TXD2)-Pad28)") (class "Default")
      (node (ref "IC2") (pin "28") (pinfunction "PH1(TXD2)_28") (pintype "bidirectional"))
    )
    (net (code "98") (name "unconnected-(IC2-PH6(OC2B)-Pad40)") (class "Default")
      (node (ref "IC2") (pin "40") (pinfunction "PH6(OC2B)_40") (pintype "bidirectional"))
    )
    (net (code "99") (name "unconnected-(IC2-PJ0(RXD3{slash}PCINT9)-Pad29)") (class "Default")
      (node (ref "IC2") (pin "29") (pinfunction "PJ0(RXD3/PCINT9)_29") (pintype "bidirectional"))
    )
    (net (code "100") (name "unconnected-(IC2-PJ1(TXD3{slash}PCINT10)-Pad30)") (class "Default")
      (node (ref "IC2") (pin "30") (pinfunction "PJ1(TXD3/PCINT10)_30") (pintype "bidirectional"))
    )
    (net (code "101") (name "unconnected-(IC2-PK4(ADC12{slash}PCINT20)-Pad19)") (class "Default")
      (node (ref "IC2") (pin "19") (pinfunction "PK4(ADC12/PCINT20)_19") (pintype "bidirectional"))
    )
    (net (code "102") (name "unconnected-(IC2-PK5(ADC13{slash}PCINT21)-Pad20)") (class "Default")
      (node (ref "IC2") (pin "20") (pinfunction "PK5(ADC13/PCINT21)_20") (pintype "bidirectional"))
    )
    (net (code "103") (name "unconnected-(IC2-PK6(ADC14{slash}PCINT22)-Pad21)") (class "Default")
      (node (ref "IC2") (pin "21") (pinfunction "PK6(ADC14/PCINT22)_21") (pintype "bidirectional"))
    )
    (net (code "104") (name "unconnected-(IC2-PK7(ADC15{slash}PCINT23)-Pad22)") (class "Default")
      (node (ref "IC2") (pin "22") (pinfunction "PK7(ADC15/PCINT23)_22") (pintype "bidirectional"))
    )
    (net (code "105") (name "unconnected-(IC2-PL0(ICP4)-Pad76)") (class "Default")
      (node (ref "IC2") (pin "76") (pinfunction "PL0(ICP4)_76") (pintype "bidirectional"))
    )
    (net (code "106") (name "unconnected-(IC2-PL1(ICP5)-Pad75)") (class "Default")
      (node (ref "IC2") (pin "75") (pinfunction "PL1(ICP5)_75") (pintype "bidirectional"))
    )
    (net (code "107") (name "unconnected-(IC2-PL2(T5)-Pad74)") (class "Default")
      (node (ref "IC2") (pin "74") (pinfunction "PL2(T5)_74") (pintype "bidirectional"))
    )
    (net (code "108") (name "unconnected-(IC2-PL3(OC5A)-Pad73)") (class "Default")
      (node (ref "IC2") (pin "73") (pinfunction "PL3(OC5A)_73") (pintype "bidirectional"))
    )
    (net (code "109") (name "unconnected-(IC2-PL4(OC5B)-Pad72)") (class "Default")
      (node (ref "IC2") (pin "72") (pinfunction "PL4(OC5B)_72") (pintype "bidirectional"))
    )
    (net (code "110") (name "unconnected-(IC2-PL5(OC5C)-Pad71)") (class "Default")
      (node (ref "IC2") (pin "71") (pinfunction "PL5(OC5C)_71") (pintype "bidirectional"))
    )
    (net (code "111") (name "unconnected-(IC2-PL6-Pad70)") (class "Default")
      (node (ref "IC2") (pin "70") (pinfunction "PL6_70") (pintype "bidirectional"))
    )
    (net (code "112") (name "unconnected-(IC2-PL7-Pad69)") (class "Default")
      (node (ref "IC2") (pin "69") (pinfunction "PL7_69") (pintype "bidirectional"))
    )
    (net (code "113") (name "unconnected-(IC2-~{RESET}-Pad1)") (class "Default")
      (node (ref "IC2") (pin "1") (pinfunction "~{RESET}_1") (pintype "bidirectional"))
    )
  )
)
